# USB_Comms.net
KiCad netlist of a schematic drawn in Altium Designer
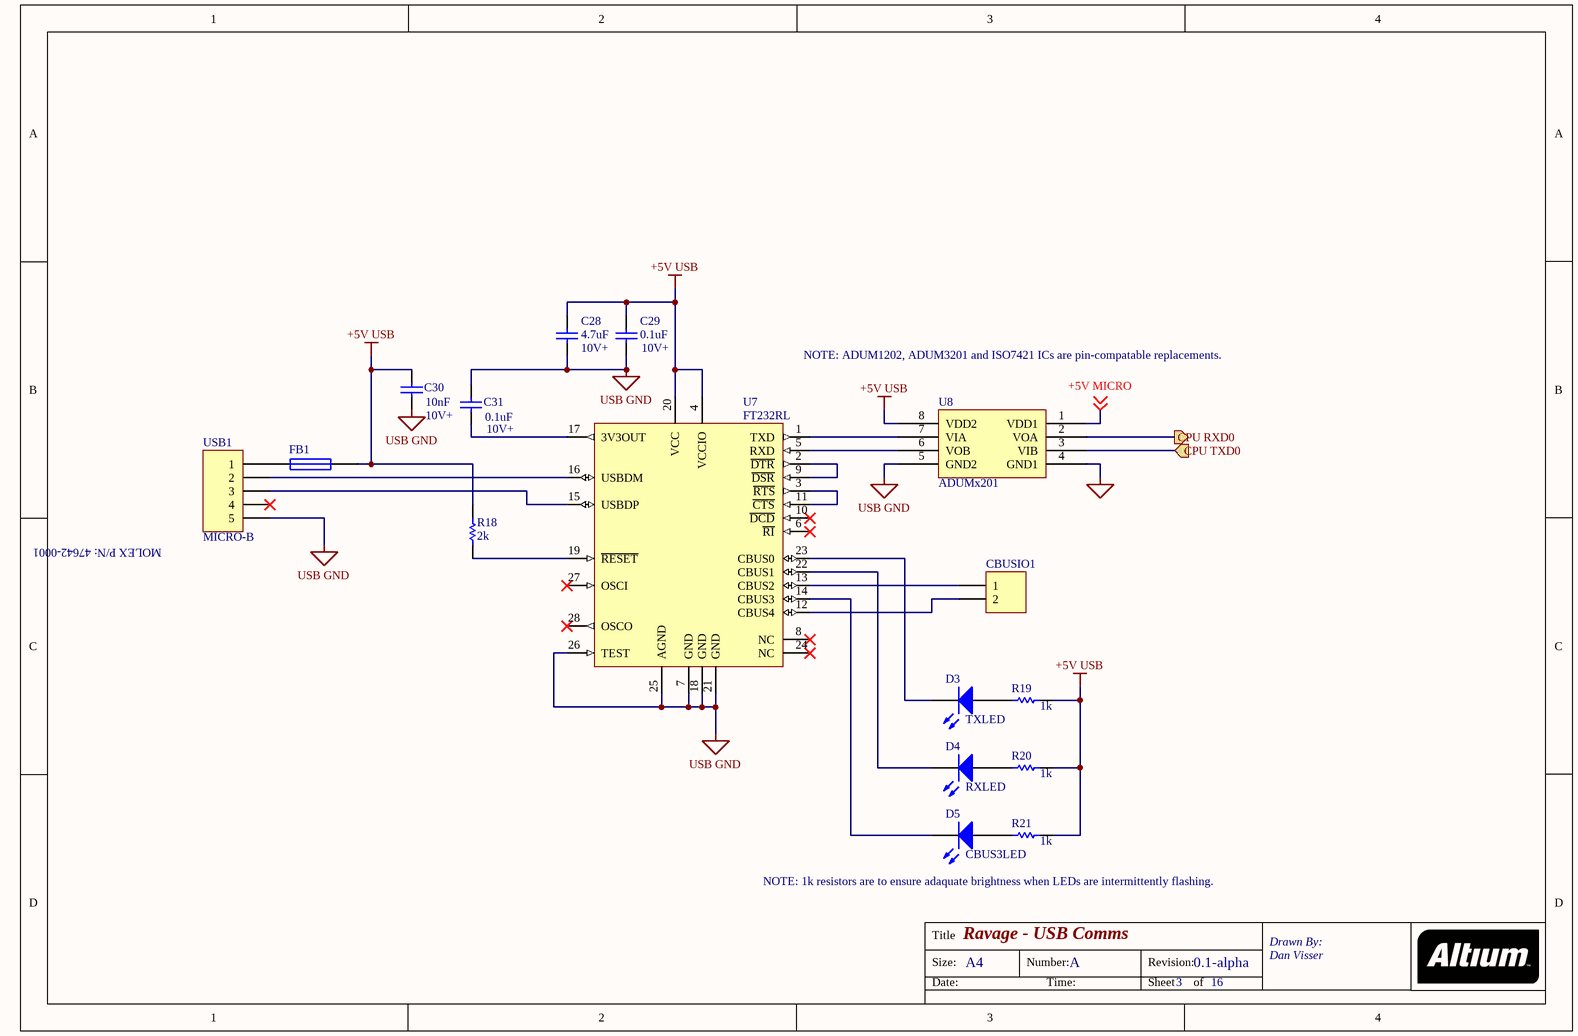
[diagram p0: USB Comms.SchDoc]

(export (version "E")
  (design (tool "Eeschema 10.0.6"))
  (components
    (comp (ref "C28")
      (value "4.7uF")
      (footprint "RAD-0.3")
      (description "Capacitor")
      (fields (field (name "PUBLISHER") "Altium Limited"))
      (libsource (lib "Miscellaneous Devices") (part "Cap"))
    )
    (comp (ref "C29")
      (value "0.1uF")
      (footprint "RAD-0.3")
      (description "Capacitor")
      (fields (field (name "PUBLISHER") "Altium Limited"))
      (libsource (lib "Miscellaneous Devices") (part "Cap"))
    )
    (comp (ref "C30")
      (value "10nF")
      (footprint "RAD-0.3")
      (description "Capacitor")
      (fields (field (name "PUBLISHER") "Altium Limited"))
      (libsource (lib "Miscellaneous Devices") (part "Cap"))
    )
    (comp (ref "C31")
      (value "0.1uF")
      (footprint "RAD-0.3")
      (description "Capacitor")
      (fields (field (name "PUBLISHER") "Altium Limited"))
      (libsource (lib "Miscellaneous Devices") (part "Cap"))
    )
    (comp (ref "CBUSIO1")
      (value "~")
      (footprint "HDR1X2")
      (description "Header, 2-Pin")
      (fields (field (name "PUBLISHER") "Altium Limited"))
      (libsource (lib "Miscellaneous Connectors") (part "Header 2"))
    )
    (comp (ref "D3")
      (value "TXLED")
      (footprint "LED-0")
      (description "Typical INFRARED GaAs LED")
      (fields (field (name "PUBLISHER") "Altium Limited"))
      (libsource (lib "Miscellaneous Devices") (part "LED0"))
    )
    (comp (ref "D4")
      (value "RXLED")
      (footprint "LED-0")
      (description "Typical INFRARED GaAs LED")
      (fields (field (name "PUBLISHER") "Altium Limited"))
      (libsource (lib "Miscellaneous Devices") (part "LED0"))
    )
    (comp (ref "D5")
      (value "CBUS3LED")
      (footprint "LED-0")
      (description "Typical INFRARED GaAs LED")
      (fields (field (name "PUBLISHER") "Altium Limited"))
      (libsource (lib "Miscellaneous Devices") (part "LED0"))
    )
    (comp (ref "FB1")
      (value "~")
      (footprint "PIN-W2/E2.8")
      (fields (field (name "PUBLISHER") "Altium Limited"))
      (libsource (lib "Miscellaneous Devices") (part "Fuse 1"))
    )
    (comp (ref "R18")
      (value "2k")
      (footprint "AXIAL-0.3")
      (description "Resistor")
      (fields (field (name "PUBLISHER") "Altium Limited"))
      (libsource (lib "Miscellaneous Devices") (part "Res1"))
    )
    (comp (ref "R19")
      (value "1k")
      (footprint "AXIAL-0.3")
      (description "Resistor")
      (fields (field (name "PUBLISHER") "Altium Limited"))
      (libsource (lib "Miscellaneous Devices") (part "Res1"))
    )
    (comp (ref "R20")
      (value "1k")
      (footprint "AXIAL-0.3")
      (description "Resistor")
      (fields (field (name "PUBLISHER") "Altium Limited"))
      (libsource (lib "Miscellaneous Devices") (part "Res1"))
    )
    (comp (ref "R21")
      (value "1k")
      (footprint "AXIAL-0.3")
      (description "Resistor")
      (fields (field (name "PUBLISHER") "Altium Limited"))
      (libsource (lib "Miscellaneous Devices") (part "Res1"))
    )
    (comp (ref "U7")
      (value "FT232RL")
      (footprint "SSOP-28_M")
      (description "USB UART Asynchronous Serial Data Transfer Chip, SSOP-28, Tray")
      (fields (field (name "PUBLISHER") "Altium Limited"))
      (libsource (lib "FTDI Communication UART") (part "FT232RL-Tray"))
    )
    (comp (ref "U8") (value "ADUMx201") (libsource (lib "FreeEMS Schematic Library") (part "ADUM3201")))
    (comp (ref "USB1")
      (value "MICRO-B")
      (footprint "HDR1X5")
      (description "Header, 5-Pin")
      (fields (field (name "PUBLISHER") "Altium Limited"))
      (libsource (lib "Miscellaneous Connectors") (part "Header 5"))
    )
  )
  (nets
    (net (code "1") (name "+5V MICRO") (class "Default")
      (node (ref "U8") (pin "1") (pinfunction "VDD1_1") (pintype "passive"))
    )
    (net (code "2") (name "+5V USB") (class "Default")
      (node (ref "C28") (pin "2") (pinfunction "2_2") (pintype "passive"))
      (node (ref "C29") (pin "2") (pinfunction "2_2") (pintype "passive"))
      (node (ref "C30") (pin "2") (pinfunction "2_2") (pintype "passive"))
      (node (ref "FB1") (pin "2") (pinfunction "2_2") (pintype "passive"))
      (node (ref "R18") (pin "2") (pinfunction "2_2") (pintype "passive"))
      (node (ref "R19") (pin "2") (pinfunction "2_2") (pintype "passive"))
      (node (ref "R20") (pin "2") (pinfunction "2_2") (pintype "passive"))
      (node (ref "R21") (pin "2") (pinfunction "2_2") (pintype "passive"))
      (node (ref "U7") (pin "20") (pinfunction "VCC_20") (pintype "power_in"))
      (node (ref "U7") (pin "4") (pinfunction "VCCIO_4") (pintype "power_in"))
      (node (ref "U8") (pin "8") (pinfunction "VDD2_8") (pintype "passive"))
    )
    (net (code "3") (name "/CPU RXD0") (class "Default")
      (node (ref "U8") (pin "2") (pinfunction "VOA_2") (pintype "passive"))
    )
    (net (code "4") (name "/CPU TXD0") (class "Default")
      (node (ref "U8") (pin "3") (pinfunction "VIB_3") (pintype "passive"))
    )
    (net (code "5") (name "<NO NET>") (class "Default")
      (node (ref "U8") (pin "4") (pinfunction "GND1_4") (pintype "passive"))
    )
    (net (code "6") (name "Net-(D3-A)") (class "Default")
      (node (ref "D3") (pin "1") (pinfunction "A_1") (pintype "passive"))
      (node (ref "R19") (pin "1") (pinfunction "1_1") (pintype "passive"))
    )
    (net (code "7") (name "Net-(D3-K)") (class "Default")
      (node (ref "D3") (pin "2") (pinfunction "K_2") (pintype "passive"))
      (node (ref "U7") (pin "23") (pinfunction "CBUS0_23") (pintype "bidirectional"))
    )
    (net (code "8") (name "Net-(D4-A)") (class "Default")
      (node (ref "D4") (pin "1") (pinfunction "A_1") (pintype "passive"))
      (node (ref "R20") (pin "1") (pinfunction "1_1") (pintype "passive"))
    )
    (net (code "9") (name "Net-(D4-K)") (class "Default")
      (node (ref "D4") (pin "2") (pinfunction "K_2") (pintype "passive"))
      (node (ref "U7") (pin "22") (pinfunction "CBUS1_22") (pintype "bidirectional"))
    )
    (net (code "10") (name "Net-(D5-A)") (class "Default")
      (node (ref "D5") (pin "1") (pinfunction "A_1") (pintype "passive"))
      (node (ref "R21") (pin "1") (pinfunction "1_1") (pintype "passive"))
    )
    (net (code "11") (name "Net-(D5-K)") (class "Default")
      (node (ref "D5") (pin "2") (pinfunction "K_2") (pintype "passive"))
      (node (ref "U7") (pin "14") (pinfunction "CBUS3_14") (pintype "bidirectional"))
    )
    (net (code "12") (name "Net-(U7-3V3OUT)") (class "Default")
      (node (ref "C31") (pin "1") (pinfunction "1_1") (pintype "passive"))
      (node (ref "U7") (pin "17") (pinfunction "3V3OUT_17") (pintype "output"))
    )
    (net (code "13") (name "Net-(U7-CBUS2)") (class "Default")
      (node (ref "CBUSIO1") (pin "1") (pinfunction "1_1") (pintype "passive"))
      (node (ref "U7") (pin "13") (pinfunction "CBUS2_13") (pintype "bidirectional"))
    )
    (net (code "14") (name "Net-(U7-CBUS4)") (class "Default")
      (node (ref "CBUSIO1") (pin "2") (pinfunction "2_2") (pintype "passive"))
      (node (ref "U7") (pin "12") (pinfunction "CBUS4_12") (pintype "bidirectional"))
    )
    (net (code "15") (name "Net-(U7-RXD)") (class "Default")
      (node (ref "U7") (pin "5") (pinfunction "RXD_5") (pintype "input"))
      (node (ref "U8") (pin "6") (pinfunction "VOB_6") (pintype "passive"))
    )
    (net (code "16") (name "Net-(U7-TXD)") (class "Default")
      (node (ref "U7") (pin "1") (pinfunction "TXD_1") (pintype "output"))
      (node (ref "U8") (pin "7") (pinfunction "VIA_7") (pintype "passive"))
    )
    (net (code "17") (name "Net-(U7-USBDM)") (class "Default")
      (node (ref "U7") (pin "16") (pinfunction "USBDM_16") (pintype "bidirectional"))
      (node (ref "USB1") (pin "2") (pinfunction "2_2") (pintype "passive"))
    )
    (net (code "18") (name "Net-(U7-USBDP)") (class "Default")
      (node (ref "U7") (pin "15") (pinfunction "USBDP_15") (pintype "bidirectional"))
      (node (ref "USB1") (pin "3") (pinfunction "3_3") (pintype "passive"))
    )
    (net (code "19") (name "Net-(U7-~{CTS})") (class "Default")
      (node (ref "U7") (pin "11") (pinfunction "~{CTS}_11") (pintype "input"))
      (node (ref "U7") (pin "3") (pinfunction "~{RTS}_3") (pintype "output"))
    )
    (net (code "20") (name "Net-(U7-~{DSR})") (class "Default")
      (node (ref "U7") (pin "2") (pinfunction "~{DTR}_2") (pintype "output"))
      (node (ref "U7") (pin "9") (pinfunction "~{DSR}_9") (pintype "input"))
    )
    (net (code "21") (name "Net-(U7-~{RESET})") (class "Default")
      (node (ref "R18") (pin "1") (pinfunction "1_1") (pintype "passive"))
      (node (ref "U7") (pin "19") (pinfunction "~{RESET}_19") (pintype "input"))
    )
    (net (code "22") (name "USB GND") (class "Default")
      (node (ref "C28") (pin "1") (pinfunction "1_1") (pintype "passive"))
      (node (ref "C29") (pin "1") (pinfunction "1_1") (pintype "passive"))
      (node (ref "C30") (pin "1") (pinfunction "1_1") (pintype "passive"))
      (node (ref "C31") (pin "2") (pinfunction "2_2") (pintype "passive"))
      (node (ref "U7") (pin "18") (pinfunction "GND_18") (pintype "power_in"))
      (node (ref "U7") (pin "21") (pinfunction "GND_21") (pintype "power_in"))
      (node (ref "U7") (pin "25") (pinfunction "AGND_25") (pintype "power_in"))
      (node (ref "U7") (pin "26") (pinfunction "TEST_26") (pintype "input"))
      (node (ref "U7") (pin "7") (pinfunction "GND_7") (pintype "power_in"))
      (node (ref "U8") (pin "5") (pinfunction "GND2_5") (pintype "passive"))
      (node (ref "USB1") (pin "5") (pinfunction "5_5") (pintype "passive"))
    )
    (net (code "23") (name "unconnected-(FB1-Pad1)") (class "Default")
      (node (ref "FB1") (pin "1") (pinfunction "1_1") (pintype "passive"))
    )
    (net (code "24") (name "unconnected-(U7-NC-Pad8)") (class "Default")
      (node (ref "U7") (pin "8") (pinfunction "NC_8") (pintype "passive+no_connect"))
    )
    (net (code "25") (name "unconnected-(U7-NC-Pad24)") (class "Default")
      (node (ref "U7") (pin "24") (pinfunction "NC_24") (pintype "passive+no_connect"))
    )
    (net (code "26") (name "unconnected-(U7-OSCI-Pad27)") (class "Default")
      (node (ref "U7") (pin "27") (pinfunction "OSCI_27") (pintype "input+no_connect"))
    )
    (net (code "27") (name "unconnected-(U7-OSCO-Pad28)") (class "Default")
      (node (ref "U7") (pin "28") (pinfunction "OSCO_28") (pintype "output+no_connect"))
    )
    (net (code "28") (name "unconnected-(U7-~{DCD}-Pad10)") (class "Default")
      (node (ref "U7") (pin "10") (pinfunction "~{DCD}_10") (pintype "input+no_connect"))
    )
    (net (code "29") (name "unconnected-(U7-~{RI}-Pad6)") (class "Default")
      (node (ref "U7") (pin "6") (pinfunction "~{RI}_6") (pintype "input+no_connect"))
    )
    (net (code "30") (name "unconnected-(USB1-Pad1)") (class "Default")
      (node (ref "USB1") (pin "1") (pinfunction "1_1") (pintype "passive"))
    )
    (net (code "31") (name "unconnected-(USB1-Pad4)") (class "Default")
      (node (ref "USB1") (pin "4") (pinfunction "4_4") (pintype "passive+no_connect"))
    )
  )
)
